# EEPROM_MAC.net
KiCad netlist of a schematic drawn in Altium Designer
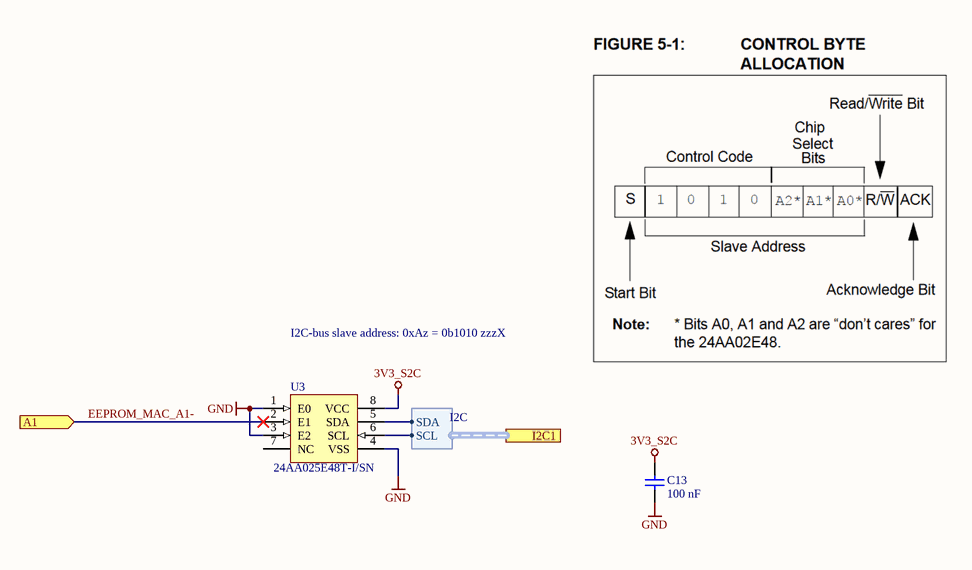
[diagram p0: EEPROM_MAC.SchDoc]

(export (version "E")
  (design (tool "Eeschema 10.0.6"))
  (components
    (comp (ref "C13")
      (value "100 nF")
      (footprint "C_0603_TE")
      (description "Generic capacitor")
      (fields
        (field (name "TOLERANCE") "10 %")
        (field (name "MANUFACTURER PART NUMBER") "UZgen_C_0603_100nF_50V_X7R")
        (field (name "CREATED FROM") "AGeiger")
      )
      (libsource (lib "user") (part "CAP-NP"))
    )
    (comp (ref "U3")
      (value "24AA025E48T-I/SN")
      (footprint "D0008A_N")
      (description "2Kbit I2C SOP-8 EEPROM ROHS")
      (fields
        (field (name "MANUFACTURER") "Microchip Tech")
        (field (name "LCSC PART NUMBER") "C2060925")
        (field (name "CREATED FROM") "FRosner")
      )
      (libsource (lib "user") (part "24AA025E48T"))
    )
  )
  (nets
    (net (code "2") (name "/EEPROM_MAC_A1-") (class "Default")
      (node (ref "U3") (pin "2") (pinfunction "E1_2") (pintype "input+no_connect"))
    )
    (net (code "3") (name "/SCL") (class "Default")
      (node (ref "U3") (pin "6") (pinfunction "SCL_6") (pintype "input"))
    )
    (net (code "4") (name "/SDA") (class "Default")
      (node (ref "U3") (pin "5") (pinfunction "SDA_5") (pintype "open_collector"))
    )
    (net (code "6") (name "3V3_S2C") (class "Default")
      (node (ref "C13") (pin "1") (pinfunction "1_1") (pintype "passive"))
      (node (ref "U3") (pin "8") (pinfunction "VCC_8") (pintype "power_in"))
    )
    (net (code "7") (name "GND") (class "Default")
      (node (ref "C13") (pin "2") (pinfunction "2_2") (pintype "passive"))
      (node (ref "U3") (pin "1") (pinfunction "E0_1") (pintype "input"))
      (node (ref "U3") (pin "3") (pinfunction "E2_3") (pintype "input"))
      (node (ref "U3") (pin "4") (pinfunction "VSS_4") (pintype "power_in"))
    )
    (net (code "8") (name "unconnected-(U3-NC-Pad7)") (class "Default")
      (node (ref "U3") (pin "7") (pinfunction "NC_7") (pintype "passive"))
    )
  )
)
